# nixie_clock.net
KiCad netlist of a schematic drawn in EAGLE
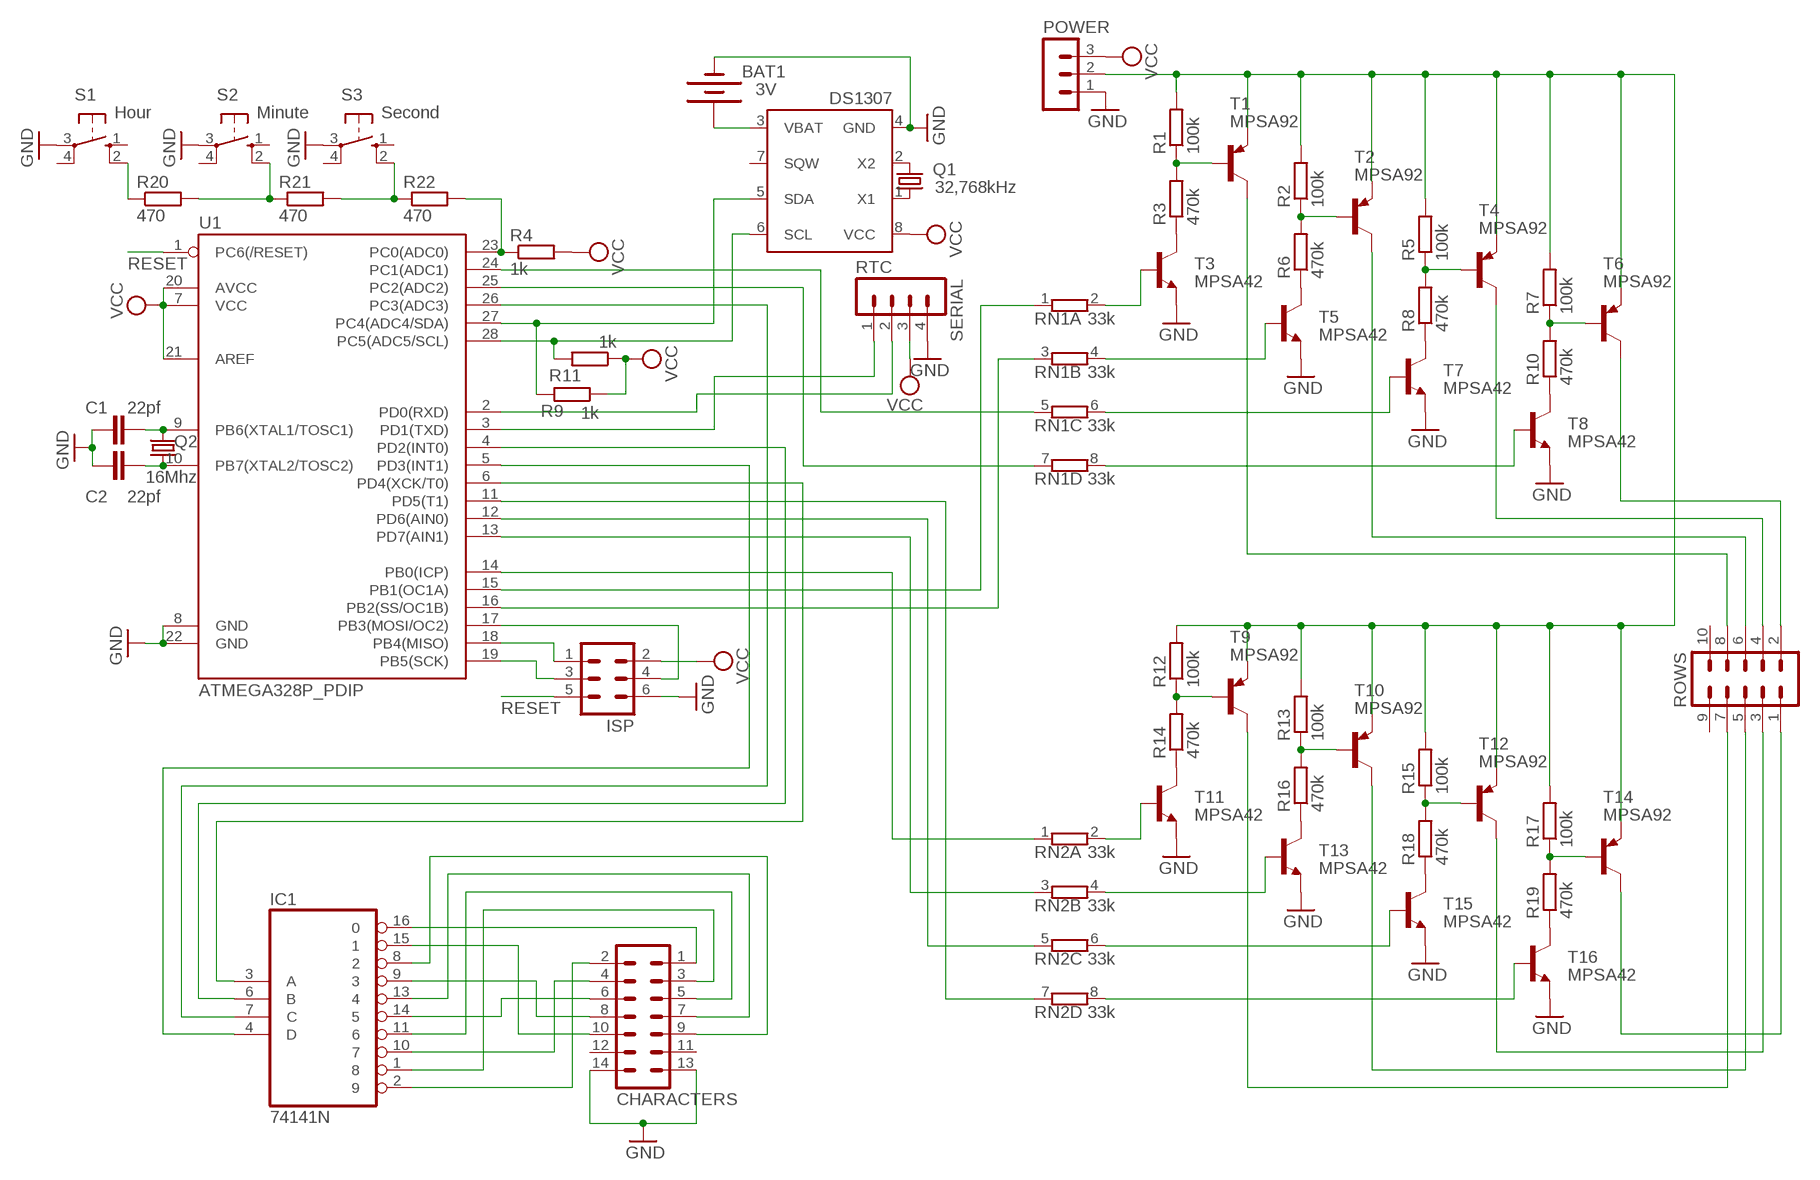
[diagram p0: schematic, sheet 1]

(export (version "E")
  (design (tool "Eeschema 10.0.6"))
  (components
    (comp (ref "BAT1")
      (value "3V")
      (footprint "eagle-import:BATTCOM_20MM_PTH")
      (libsource (lib "eagle-import") (part "BATTERY20PTH"))
    )
    (comp (ref "C1")
      (value "22pf")
      (footprint "eagle-import:CAP-PTH-SMALLEZ")
      (libsource (lib "eagle-import") (part "CAPEZ"))
    )
    (comp (ref "C2")
      (value "22pf")
      (footprint "eagle-import:CAP-PTH-SMALLEZ")
      (libsource (lib "eagle-import") (part "CAPEZ"))
    )
    (comp (ref "CHARACTERS")
      (value "MA07-2")
      (footprint "eagle-import:MA07-2")
      (libsource (lib "eagle-import") (part "MA07-2"))
    )
    (comp (ref "IC1")
      (value "74141N")
      (footprint "eagle-import:DIL16")
      (libsource (lib "eagle-import") (part "74141N"))
    )
    (comp (ref "ISP")
      (value "MA03-2")
      (footprint "eagle-import:MA03-2")
      (libsource (lib "eagle-import") (part "MA03-2"))
    )
    (comp (ref "POWER")
      (value "MA03-1")
      (footprint "eagle-import:MA03-1")
      (libsource (lib "eagle-import") (part "MA03-1"))
    )
    (comp (ref "Q1")
      (value "32,768kHz")
      (footprint "eagle-import:TC26V")
      (libsource (lib "eagle-import") (part "CRYSTALTC26V"))
    )
    (comp (ref "Q2")
      (value "16Mhz")
      (footprint "eagle-import:HC49_S")
      (libsource (lib "eagle-import") (part "CRYSTALHC49S"))
    )
    (comp (ref "R1")
      (value "100k")
      (footprint "eagle-import:0207_2V")
      (libsource (lib "eagle-import") (part "R-EU_0207/2V"))
    )
    (comp (ref "R2")
      (value "100k")
      (footprint "eagle-import:0207_2V")
      (libsource (lib "eagle-import") (part "R-EU_0207/2V"))
    )
    (comp (ref "R3")
      (value "470k")
      (footprint "eagle-import:0204_7")
      (libsource (lib "eagle-import") (part "R-EU_0204/7"))
    )
    (comp (ref "R4")
      (value "1k")
      (footprint "eagle-import:0204_7")
      (libsource (lib "eagle-import") (part "R-EU_0204/7"))
    )
    (comp (ref "R5")
      (value "100k")
      (footprint "eagle-import:0207_2V")
      (libsource (lib "eagle-import") (part "R-EU_0207/2V"))
    )
    (comp (ref "R6")
      (value "470k")
      (footprint "eagle-import:0204_7")
      (libsource (lib "eagle-import") (part "R-EU_0204/7"))
    )
    (comp (ref "R7")
      (value "100k")
      (footprint "eagle-import:0207_2V")
      (libsource (lib "eagle-import") (part "R-EU_0207/2V"))
    )
    (comp (ref "R8")
      (value "470k")
      (footprint "eagle-import:0204_7")
      (libsource (lib "eagle-import") (part "R-EU_0204/7"))
    )
    (comp (ref "R9")
      (value "1k")
      (footprint "eagle-import:0204_7")
      (libsource (lib "eagle-import") (part "R-EU_0204/7"))
    )
    (comp (ref "R10")
      (value "470k")
      (footprint "eagle-import:0204_7")
      (libsource (lib "eagle-import") (part "R-EU_0204/7"))
    )
    (comp (ref "R11")
      (value "1k")
      (footprint "eagle-import:0204_7")
      (libsource (lib "eagle-import") (part "R-EU_0204/7"))
    )
    (comp (ref "R12")
      (value "100k")
      (footprint "eagle-import:0207_2V")
      (libsource (lib "eagle-import") (part "R-EU_0207/2V"))
    )
    (comp (ref "R13")
      (value "100k")
      (footprint "eagle-import:0207_2V")
      (libsource (lib "eagle-import") (part "R-EU_0207/2V"))
    )
    (comp (ref "R14")
      (value "470k")
      (footprint "eagle-import:0204_7")
      (libsource (lib "eagle-import") (part "R-EU_0204/7"))
    )
    (comp (ref "R15")
      (value "100k")
      (footprint "eagle-import:0207_2V")
      (libsource (lib "eagle-import") (part "R-EU_0207/2V"))
    )
    (comp (ref "R16")
      (value "470k")
      (footprint "eagle-import:0204_7")
      (libsource (lib "eagle-import") (part "R-EU_0204/7"))
    )
    (comp (ref "R17")
      (value "100k")
      (footprint "eagle-import:0207_2V")
      (libsource (lib "eagle-import") (part "R-EU_0207/2V"))
    )
    (comp (ref "R18")
      (value "470k")
      (footprint "eagle-import:0204_7")
      (libsource (lib "eagle-import") (part "R-EU_0204/7"))
    )
    (comp (ref "R19")
      (value "470k")
      (footprint "eagle-import:0204_7")
      (libsource (lib "eagle-import") (part "R-EU_0204/7"))
    )
    (comp (ref "R20")
      (value "470")
      (footprint "eagle-import:0204_7")
      (libsource (lib "eagle-import") (part "R-EU_0204/7"))
    )
    (comp (ref "R21")
      (value "470")
      (footprint "eagle-import:0204_7")
      (libsource (lib "eagle-import") (part "R-EU_0204/7"))
    )
    (comp (ref "R22")
      (value "470")
      (footprint "eagle-import:0204_7")
      (libsource (lib "eagle-import") (part "R-EU_0204/7"))
    )
    (comp (ref "RN1")
      (value "33k")
      (footprint "eagle-import:SIL8")
      (libsource (lib "eagle-import") (part "E4R"))
    )
    (comp (ref "RN2")
      (value "33k")
      (footprint "eagle-import:SIL8")
      (libsource (lib "eagle-import") (part "E4R"))
    )
    (comp (ref "ROWS")
      (value "MA05-2")
      (footprint "eagle-import:MA05-2")
      (libsource (lib "eagle-import") (part "MA05-2"))
    )
    (comp (ref "RTC")
      (value "DS1307")
      (footprint "eagle-import:DIL08")
      (libsource (lib "eagle-import") (part "DS1307"))
    )
    (comp (ref "S1")
      (value "Hour")
      (footprint "eagle-import:B3F-10XX")
      (fields (field (name "MPN") "B3F-1000"))
      (libsource (lib "eagle-import") (part "10-XX"))
    )
    (comp (ref "S2")
      (value "Minute")
      (footprint "eagle-import:B3F-10XX")
      (fields (field (name "MPN") "B3F-1000"))
      (libsource (lib "eagle-import") (part "10-XX"))
    )
    (comp (ref "S3")
      (value "Second")
      (footprint "eagle-import:B3F-10XX")
      (fields (field (name "MPN") "B3F-1000"))
      (libsource (lib "eagle-import") (part "10-XX"))
    )
    (comp (ref "SERIAL")
      (value "MA04-1")
      (footprint "eagle-import:MA04-1")
      (libsource (lib "eagle-import") (part "MA04-1"))
    )
    (comp (ref "T1")
      (value "MPSA92")
      (footprint "eagle-import:TO92-EBC")
      (libsource (lib "eagle-import") (part "-PNP-TO92-EBCMPSA92"))
    )
    (comp (ref "T2")
      (value "MPSA92")
      (footprint "eagle-import:TO92-EBC")
      (libsource (lib "eagle-import") (part "-PNP-TO92-EBCMPSA92"))
    )
    (comp (ref "T3")
      (value "MPSA42")
      (footprint "eagle-import:TO92-EBC")
      (libsource (lib "eagle-import") (part "-NPN-TO92-EBCMPSA42"))
    )
    (comp (ref "T4")
      (value "MPSA92")
      (footprint "eagle-import:TO92-EBC")
      (libsource (lib "eagle-import") (part "-PNP-TO92-EBCMPSA92"))
    )
    (comp (ref "T5")
      (value "MPSA42")
      (footprint "eagle-import:TO92-EBC")
      (libsource (lib "eagle-import") (part "-NPN-TO92-EBCMPSA42"))
    )
    (comp (ref "T6")
      (value "MPSA92")
      (footprint "eagle-import:TO92-EBC")
      (libsource (lib "eagle-import") (part "-PNP-TO92-EBCMPSA92"))
    )
    (comp (ref "T7")
      (value "MPSA42")
      (footprint "eagle-import:TO92-EBC")
      (libsource (lib "eagle-import") (part "-NPN-TO92-EBCMPSA42"))
    )
    (comp (ref "T8")
      (value "MPSA42")
      (footprint "eagle-import:TO92-EBC")
      (libsource (lib "eagle-import") (part "-NPN-TO92-EBCMPSA42"))
    )
    (comp (ref "T9")
      (value "MPSA92")
      (footprint "eagle-import:TO92-EBC")
      (libsource (lib "eagle-import") (part "-PNP-TO92-EBCMPSA92"))
    )
    (comp (ref "T10")
      (value "MPSA92")
      (footprint "eagle-import:TO92-EBC")
      (libsource (lib "eagle-import") (part "-PNP-TO92-EBCMPSA92"))
    )
    (comp (ref "T11")
      (value "MPSA42")
      (footprint "eagle-import:TO92-EBC")
      (libsource (lib "eagle-import") (part "-NPN-TO92-EBCMPSA42"))
    )
    (comp (ref "T12")
      (value "MPSA92")
      (footprint "eagle-import:TO92-EBC")
      (libsource (lib "eagle-import") (part "-PNP-TO92-EBCMPSA92"))
    )
    (comp (ref "T13")
      (value "MPSA42")
      (footprint "eagle-import:TO92-EBC")
      (libsource (lib "eagle-import") (part "-NPN-TO92-EBCMPSA42"))
    )
    (comp (ref "T14")
      (value "MPSA92")
      (footprint "eagle-import:TO92-EBC")
      (libsource (lib "eagle-import") (part "-PNP-TO92-EBCMPSA92"))
    )
    (comp (ref "T15")
      (value "MPSA42")
      (footprint "eagle-import:TO92-EBC")
      (libsource (lib "eagle-import") (part "-NPN-TO92-EBCMPSA42"))
    )
    (comp (ref "T16")
      (value "MPSA42")
      (footprint "eagle-import:TO92-EBC")
      (libsource (lib "eagle-import") (part "-NPN-TO92-EBCMPSA42"))
    )
    (comp (ref "U1")
      (value "ATMEGA328P_PDIP")
      (footprint "eagle-import:DIL28-3")
      (libsource (lib "eagle-import") (part "ATMEGA328P_PDIP"))
    )
  )
  (nets
    (net (code "1") (name "/RESET") (class "Default")
      (node (ref "ISP") (pin "5") (pinfunction "5_5") (pintype "passive"))
      (node (ref "U1") (pin "1") (pinfunction "PC6(/RESET)_1") (pintype "bidirectional"))
    )
    (net (code "2") (name "GND") (class "Default")
      (node (ref "BAT1") (pin "2") (pinfunction "-_2") (pintype "power_in"))
      (node (ref "C1") (pin "1") (pinfunction "1_1") (pintype "passive"))
      (node (ref "C2") (pin "1") (pinfunction "1_1") (pintype "passive"))
      (node (ref "CHARACTERS") (pin "13") (pinfunction "13_13") (pintype "passive"))
      (node (ref "CHARACTERS") (pin "14") (pinfunction "14_14") (pintype "passive"))
      (node (ref "ISP") (pin "6") (pinfunction "6_6") (pintype "passive"))
      (node (ref "POWER") (pin "1") (pinfunction "1_1") (pintype "passive"))
      (node (ref "RTC") (pin "4") (pinfunction "GND_4") (pintype "power_in"))
      (node (ref "S1") (pin "3") (pinfunction "P_3") (pintype "passive"))
      (node (ref "S2") (pin "3") (pinfunction "P_3") (pintype "passive"))
      (node (ref "S3") (pin "3") (pinfunction "P_3") (pintype "passive"))
      (node (ref "SERIAL") (pin "4") (pinfunction "4_4") (pintype "passive"))
      (node (ref "T11") (pin "E") (pinfunction "E_E") (pintype "passive"))
      (node (ref "T13") (pin "E") (pinfunction "E_E") (pintype "passive"))
      (node (ref "T15") (pin "E") (pinfunction "E_E") (pintype "passive"))
      (node (ref "T16") (pin "E") (pinfunction "E_E") (pintype "passive"))
      (node (ref "T3") (pin "E") (pinfunction "E_E") (pintype "passive"))
      (node (ref "T5") (pin "E") (pinfunction "E_E") (pintype "passive"))
      (node (ref "T7") (pin "E") (pinfunction "E_E") (pintype "passive"))
      (node (ref "T8") (pin "E") (pinfunction "E_E") (pintype "passive"))
      (node (ref "U1") (pin "22") (pinfunction "GND_22") (pintype "bidirectional"))
      (node (ref "U1") (pin "8") (pinfunction "GND_8") (pintype "bidirectional"))
    )
    (net (code "3") (name "Net-(BAT1-+)") (class "Default")
      (node (ref "BAT1") (pin "1") (pinfunction "+_1") (pintype "power_in"))
      (node (ref "RTC") (pin "3") (pinfunction "VBAT_3") (pintype "passive"))
    )
    (net (code "4") (name "Net-(IC1A-0)") (class "Default")
      (node (ref "CHARACTERS") (pin "1") (pinfunction "1_1") (pintype "passive"))
      (node (ref "IC1") (pin "16") (pinfunction "0_16") (pintype "open_collector"))
    )
    (net (code "5") (name "Net-(IC1A-1)") (class "Default")
      (node (ref "CHARACTERS") (pin "10") (pinfunction "10_10") (pintype "passive"))
      (node (ref "IC1") (pin "15") (pinfunction "1_15") (pintype "open_collector"))
    )
    (net (code "6") (name "Net-(IC1A-2)") (class "Default")
      (node (ref "CHARACTERS") (pin "9") (pinfunction "9_9") (pintype "passive"))
      (node (ref "IC1") (pin "8") (pinfunction "2_8") (pintype "open_collector"))
    )
    (net (code "7") (name "Net-(IC1A-3)") (class "Default")
      (node (ref "CHARACTERS") (pin "8") (pinfunction "8_8") (pintype "passive"))
      (node (ref "IC1") (pin "9") (pinfunction "3_9") (pintype "open_collector"))
    )
    (net (code "8") (name "Net-(IC1A-4)") (class "Default")
      (node (ref "CHARACTERS") (pin "7") (pinfunction "7_7") (pintype "passive"))
      (node (ref "IC1") (pin "13") (pinfunction "4_13") (pintype "open_collector"))
    )
    (net (code "9") (name "Net-(IC1A-5)") (class "Default")
      (node (ref "CHARACTERS") (pin "6") (pinfunction "6_6") (pintype "passive"))
      (node (ref "IC1") (pin "14") (pinfunction "5_14") (pintype "open_collector"))
    )
    (net (code "10") (name "Net-(IC1A-6)") (class "Default")
      (node (ref "CHARACTERS") (pin "5") (pinfunction "5_5") (pintype "passive"))
      (node (ref "IC1") (pin "11") (pinfunction "6_11") (pintype "open_collector"))
    )
    (net (code "11") (name "Net-(IC1A-7)") (class "Default")
      (node (ref "CHARACTERS") (pin "4") (pinfunction "4_4") (pintype "passive"))
      (node (ref "IC1") (pin "10") (pinfunction "7_10") (pintype "open_collector"))
    )
    (net (code "12") (name "Net-(IC1A-8)") (class "Default")
      (node (ref "CHARACTERS") (pin "3") (pinfunction "3_3") (pintype "passive"))
      (node (ref "IC1") (pin "1") (pinfunction "8_1") (pintype "open_collector"))
    )
    (net (code "13") (name "Net-(IC1A-9)") (class "Default")
      (node (ref "CHARACTERS") (pin "2") (pinfunction "2_2") (pintype "passive"))
      (node (ref "IC1") (pin "2") (pinfunction "9_2") (pintype "open_collector"))
    )
    (net (code "14") (name "Net-(IC1A-A)") (class "Default")
      (node (ref "IC1") (pin "3") (pinfunction "A_3") (pintype "input"))
      (node (ref "U1") (pin "6") (pinfunction "PD4(XCK/T0)_6") (pintype "bidirectional"))
    )
    (net (code "15") (name "Net-(IC1A-B)") (class "Default")
      (node (ref "IC1") (pin "6") (pinfunction "B_6") (pintype "input"))
      (node (ref "U1") (pin "4") (pinfunction "PD2(INT0)_4") (pintype "bidirectional"))
    )
    (net (code "16") (name "Net-(IC1A-C)") (class "Default")
      (node (ref "IC1") (pin "7") (pinfunction "C_7") (pintype "input"))
      (node (ref "U1") (pin "26") (pinfunction "PC3(ADC3)_26") (pintype "bidirectional"))
    )
    (net (code "17") (name "Net-(IC1A-D)") (class "Default")
      (node (ref "IC1") (pin "4") (pinfunction "D_4") (pintype "input"))
      (node (ref "U1") (pin "5") (pinfunction "PD3(INT1)_5") (pintype "bidirectional"))
    )
    (net (code "18") (name "Net-(POWER-Pad2)") (class "Default")
      (node (ref "POWER") (pin "2") (pinfunction "2_2") (pintype "passive"))
      (node (ref "R1") (pin "2") (pinfunction "2_2") (pintype "passive"))
      (node (ref "R12") (pin "2") (pinfunction "2_2") (pintype "passive"))
      (node (ref "R13") (pin "2") (pinfunction "2_2") (pintype "passive"))
      (node (ref "R15") (pin "2") (pinfunction "2_2") (pintype "passive"))
      (node (ref "R17") (pin "2") (pinfunction "2_2") (pintype "passive"))
      (node (ref "R2") (pin "2") (pinfunction "2_2") (pintype "passive"))
      (node (ref "R5") (pin "2") (pinfunction "2_2") (pintype "passive"))
      (node (ref "R7") (pin "2") (pinfunction "2_2") (pintype "passive"))
      (node (ref "T1") (pin "E") (pinfunction "E_E") (pintype "passive"))
      (node (ref "T10") (pin "E") (pinfunction "E_E") (pintype "passive"))
      (node (ref "T12") (pin "E") (pinfunction "E_E") (pintype "passive"))
      (node (ref "T14") (pin "E") (pinfunction "E_E") (pintype "passive"))
      (node (ref "T2") (pin "E") (pinfunction "E_E") (pintype "passive"))
      (node (ref "T4") (pin "E") (pinfunction "E_E") (pintype "passive"))
      (node (ref "T6") (pin "E") (pinfunction "E_E") (pintype "passive"))
      (node (ref "T9") (pin "E") (pinfunction "E_E") (pintype "passive"))
    )
    (net (code "19") (name "Net-(R1-Pad1)") (class "Default")
      (node (ref "R1") (pin "1") (pinfunction "1_1") (pintype "passive"))
      (node (ref "R3") (pin "2") (pinfunction "2_2") (pintype "passive"))
      (node (ref "T1") (pin "B") (pinfunction "B_B") (pintype "passive"))
    )
    (net (code "20") (name "Net-(R2-Pad1)") (class "Default")
      (node (ref "R2") (pin "1") (pinfunction "1_1") (pintype "passive"))
      (node (ref "R6") (pin "2") (pinfunction "2_2") (pintype "passive"))
      (node (ref "T2") (pin "B") (pinfunction "B_B") (pintype "passive"))
    )
    (net (code "21") (name "Net-(R3-Pad1)") (class "Default")
      (node (ref "R3") (pin "1") (pinfunction "1_1") (pintype "passive"))
      (node (ref "T3") (pin "C") (pinfunction "C_C") (pintype "passive"))
    )
    (net (code "22") (name "Net-(R5-Pad1)") (class "Default")
      (node (ref "R5") (pin "1") (pinfunction "1_1") (pintype "passive"))
      (node (ref "R8") (pin "2") (pinfunction "2_2") (pintype "passive"))
      (node (ref "T4") (pin "B") (pinfunction "B_B") (pintype "passive"))
    )
    (net (code "23") (name "Net-(R6-Pad1)") (class "Default")
      (node (ref "R6") (pin "1") (pinfunction "1_1") (pintype "passive"))
      (node (ref "T5") (pin "C") (pinfunction "C_C") (pintype "passive"))
    )
    (net (code "24") (name "Net-(R8-Pad1)") (class "Default")
      (node (ref "R8") (pin "1") (pinfunction "1_1") (pintype "passive"))
      (node (ref "T7") (pin "C") (pinfunction "C_C") (pintype "passive"))
    )
    (net (code "25") (name "Net-(R10-Pad1)") (class "Default")
      (node (ref "R10") (pin "1") (pinfunction "1_1") (pintype "passive"))
      (node (ref "T8") (pin "C") (pinfunction "C_C") (pintype "passive"))
    )
    (net (code "26") (name "Net-(R10-Pad2)") (class "Default")
      (node (ref "R10") (pin "2") (pinfunction "2_2") (pintype "passive"))
      (node (ref "R7") (pin "1") (pinfunction "1_1") (pintype "passive"))
      (node (ref "T6") (pin "B") (pinfunction "B_B") (pintype "passive"))
    )
    (net (code "27") (name "Net-(R12-Pad1)") (class "Default")
      (node (ref "R12") (pin "1") (pinfunction "1_1") (pintype "passive"))
      (node (ref "R14") (pin "2") (pinfunction "2_2") (pintype "passive"))
      (node (ref "T9") (pin "B") (pinfunction "B_B") (pintype "passive"))
    )
    (net (code "28") (name "Net-(R13-Pad1)") (class "Default")
      (node (ref "R13") (pin "1") (pinfunction "1_1") (pintype "passive"))
      (node (ref "R16") (pin "2") (pinfunction "2_2") (pintype "passive"))
      (node (ref "T10") (pin "B") (pinfunction "B_B") (pintype "passive"))
    )
    (net (code "29") (name "Net-(R14-Pad1)") (class "Default")
      (node (ref "R14") (pin "1") (pinfunction "1_1") (pintype "passive"))
      (node (ref "T11") (pin "C") (pinfunction "C_C") (pintype "passive"))
    )
    (net (code "30") (name "Net-(R15-Pad1)") (class "Default")
      (node (ref "R15") (pin "1") (pinfunction "1_1") (pintype "passive"))
      (node (ref "R18") (pin "2") (pinfunction "2_2") (pintype "passive"))
      (node (ref "T12") (pin "B") (pinfunction "B_B") (pintype "passive"))
    )
    (net (code "31") (name "Net-(R16-Pad1)") (class "Default")
      (node (ref "R16") (pin "1") (pinfunction "1_1") (pintype "passive"))
      (node (ref "T13") (pin "C") (pinfunction "C_C") (pintype "passive"))
    )
    (net (code "32") (name "Net-(R17-Pad1)") (class "Default")
      (node (ref "R17") (pin "1") (pinfunction "1_1") (pintype "passive"))
      (node (ref "R19") (pin "2") (pinfunction "2_2") (pintype "passive"))
      (node (ref "T14") (pin "B") (pinfunction "B_B") (pintype "passive"))
    )
    (net (code "33") (name "Net-(R18-Pad1)") (class "Default")
      (node (ref "R18") (pin "1") (pinfunction "1_1") (pintype "passive"))
      (node (ref "T15") (pin "C") (pinfunction "C_C") (pintype "passive"))
    )
    (net (code "34") (name "Net-(R19-Pad1)") (class "Default")
      (node (ref "R19") (pin "1") (pinfunction "1_1") (pintype "passive"))
      (node (ref "T16") (pin "C") (pinfunction "C_C") (pintype "passive"))
    )
    (net (code "35") (name "Net-(RN1-Pad2)") (class "Default")
      (node (ref "RN1") (pin "2") (pinfunction "2_2") (pintype "passive"))
      (node (ref "T3") (pin "B") (pinfunction "B_B") (pintype "passive"))
    )
    (net (code "36") (name "Net-(RN1B-1)") (class "Default")
      (node (ref "RN1") (pin "3") (pinfunction "1_3") (pintype "passive"))
      (node (ref "U1") (pin "16") (pinfunction "PB2(SS/OC1B)_16") (pintype "bidirectional"))
    )
    (net (code "37") (name "Net-(RN1B-2)") (class "Default")
      (node (ref "RN1") (pin "4") (pinfunction "2_4") (pintype "passive"))
      (node (ref "T5") (pin "B") (pinfunction "B_B") (pintype "passive"))
    )
    (net (code "38") (name "Net-(RN1C-1)") (class "Default")
      (node (ref "RN1") (pin "5") (pinfunction "1_5") (pintype "passive"))
      (node (ref "U1") (pin "24") (pinfunction "PC1(ADC1)_24") (pintype "bidirectional"))
    )
    (net (code "39") (name "Net-(RN1C-2)") (class "Default")
      (node (ref "RN1") (pin "6") (pinfunction "2_6") (pintype "passive"))
      (node (ref "T7") (pin "B") (pinfunction "B_B") (pintype "passive"))
    )
    (net (code "40") (name "Net-(RN1D-1)") (class "Default")
      (node (ref "RN1") (pin "7") (pinfunction "1_7") (pintype "passive"))
      (node (ref "U1") (pin "25") (pinfunction "PC2(ADC2)_25") (pintype "bidirectional"))
    )
    (net (code "41") (name "Net-(RN1D-2)") (class "Default")
      (node (ref "RN1") (pin "8") (pinfunction "2_8") (pintype "passive"))
      (node (ref "T8") (pin "B") (pinfunction "B_B") (pintype "passive"))
    )
    (net (code "42") (name "Net-(RN2-Pad2)") (class "Default")
      (node (ref "RN2") (pin "2") (pinfunction "2_2") (pintype "passive"))
      (node (ref "T11") (pin "B") (pinfunction "B_B") (pintype "passive"))
    )
    (net (code "43") (name "Net-(RN2B-1)") (class "Default")
      (node (ref "RN2") (pin "3") (pinfunction "1_3") (pintype "passive"))
      (node (ref "U1") (pin "13") (pinfunction "PD7(AIN1)_13") (pintype "bidirectional"))
    )
    (net (code "44") (name "Net-(RN2B-2)") (class "Default")
      (node (ref "RN2") (pin "4") (pinfunction "2_4") (pintype "passive"))
      (node (ref "T13") (pin "B") (pinfunction "B_B") (pintype "passive"))
    )
    (net (code "45") (name "Net-(RN2C-1)") (class "Default")
      (node (ref "RN2") (pin "5") (pinfunction "1_5") (pintype "passive"))
      (node (ref "U1") (pin "12") (pinfunction "PD6(AIN0)_12") (pintype "bidirectional"))
    )
    (net (code "46") (name "Net-(RN2C-2)") (class "Default")
      (node (ref "RN2") (pin "6") (pinfunction "2_6") (pintype "passive"))
      (node (ref "T15") (pin "B") (pinfunction "B_B") (pintype "passive"))
    )
    (net (code "47") (name "Net-(RN2D-1)") (class "Default")
      (node (ref "RN2") (pin "7") (pinfunction "1_7") (pintype "passive"))
      (node (ref "U1") (pin "11") (pinfunction "PD5(T1)_11") (pintype "bidirectional"))
    )
    (net (code "48") (name "Net-(RN2D-2)") (class "Default")
      (node (ref "RN2") (pin "8") (pinfunction "2_8") (pintype "passive"))
      (node (ref "T16") (pin "B") (pinfunction "B_B") (pintype "passive"))
    )
    (net (code "49") (name "Net-(ROWS-Pad1)") (class "Default")
      (node (ref "ROWS") (pin "1") (pinfunction "1_1") (pintype "passive"))
      (node (ref "T14") (pin "C") (pinfunction "C_C") (pintype "passive"))
    )
    (net (code "50") (name "Net-(ROWS-Pad2)") (class "Default")
      (node (ref "ROWS") (pin "2") (pinfunction "2_2") (pintype "passive"))
      (node (ref "T6") (pin "C") (pinfunction "C_C") (pintype "passive"))
    )
    (net (code "51") (name "Net-(ROWS-Pad3)") (class "Default")
      (node (ref "ROWS") (pin "3") (pinfunction "3_3") (pintype "passive"))
      (node (ref "T12") (pin "C") (pinfunction "C_C") (pintype "passive"))
    )
    (net (code "52") (name "Net-(ROWS-Pad4)") (class "Default")
      (node (ref "ROWS") (pin "4") (pinfunction "4_4") (pintype "passive"))
      (node (ref "T4") (pin "C") (pinfunction "C_C") (pintype "passive"))
    )
    (net (code "53") (name "Net-(ROWS-Pad5)") (class "Default")
      (node (ref "ROWS") (pin "5") (pinfunction "5_5") (pintype "passive"))
      (node (ref "T10") (pin "C") (pinfunction "C_C") (pintype "passive"))
    )
    (net (code "54") (name "Net-(ROWS-Pad6)") (class "Default")
      (node (ref "ROWS") (pin "6") (pinfunction "6_6") (pintype "passive"))
      (node (ref "T2") (pin "C") (pinfunction "C_C") (pintype "passive"))
    )
    (net (code "55") (name "Net-(ROWS-Pad7)") (class "Default")
      (node (ref "ROWS") (pin "7") (pinfunction "7_7") (pintype "passive"))
      (node (ref "T9") (pin "C") (pinfunction "C_C") (pintype "passive"))
    )
    (net (code "56") (name "Net-(ROWS-Pad8)") (class "Default")
      (node (ref "ROWS") (pin "8") (pinfunction "8_8") (pintype "passive"))
      (node (ref "T1") (pin "C") (pinfunction "C_C") (pintype "passive"))
    )
    (net (code "57") (name "Net-(RTC-SCL)") (class "Default")
      (node (ref "R11") (pin "2") (pinfunction "2_2") (pintype "passive"))
      (node (ref "RTC") (pin "6") (pinfunction "SCL_6") (pintype "input"))
      (node (ref "U1") (pin "28") (pinfunction "PC5(ADC5/SCL)_28") (pintype "bidirectional"))
    )
    (net (code "58") (name "Net-(RTC-SDA)") (class "Default")
      (node (ref "R9") (pin "2") (pinfunction "2_2") (pintype "passive"))
      (node (ref "RTC") (pin "5") (pinfunction "SDA_5") (pintype "bidirectional"))
      (node (ref "U1") (pin "27") (pinfunction "PC4(ADC4/SDA)_27") (pintype "bidirectional"))
    )
    (net (code "59") (name "Net-(RTC-X1)") (class "Default")
      (node (ref "Q1") (pin "1") (pinfunction "1_1") (pintype "passive"))
      (node (ref "RTC") (pin "1") (pinfunction "X1_1") (pintype "input"))
    )
    (net (code "60") (name "Net-(RTC-X2)") (class "Default")
      (node (ref "Q1") (pin "2") (pinfunction "2_2") (pintype "passive"))
      (node (ref "RTC") (pin "2") (pinfunction "X2_2") (pintype "output"))
    )
    (net (code "61") (name "Net-(S1-S1)") (class "Default")
      (node (ref "R20") (pin "1") (pinfunction "1_1") (pintype "passive"))
      (node (ref "S1") (pin "2") (pinfunction "S1_2") (pintype "passive"))
    )
    (net (code "62") (name "Net-(S2-S1)") (class "Default")
      (node (ref "R20") (pin "2") (pinfunction "2_2") (pintype "passive"))
      (node (ref "R21") (pin "1") (pinfunction "1_1") (pintype "passive"))
      (node (ref "S2") (pin "2") (pinfunction "S1_2") (pintype "passive"))
    )
    (net (code "63") (name "Net-(S3-S1)") (class "Default")
      (node (ref "R21") (pin "2") (pinfunction "2_2") (pintype "passive"))
      (node (ref "R22") (pin "1") (pinfunction "1_1") (pintype "passive"))
      (node (ref "S3") (pin "2") (pinfunction "S1_2") (pintype "passive"))
    )
    (net (code "64") (name "Net-(U1-PB0(ICP))") (class "Default")
      (node (ref "RN2") (pin "1") (pinfunction "1_1") (pintype "passive"))
      (node (ref "U1") (pin "14") (pinfunction "PB0(ICP)_14") (pintype "bidirectional"))
    )
    (net (code "65") (name "Net-(U1-PB1(OC1A))") (class "Default")
      (node (ref "RN1") (pin "1") (pinfunction "1_1") (pintype "passive"))
      (node (ref "U1") (pin "15") (pinfunction "PB1(OC1A)_15") (pintype "bidirectional"))
    )
    (net (code "66") (name "Net-(U1-PB3(MOSI{slash}OC2))") (class "Default")
      (node (ref "ISP") (pin "4") (pinfunction "4_4") (pintype "passive"))
      (node (ref "U1") (pin "17") (pinfunction "PB3(MOSI/OC2)_17") (pintype "bidirectional"))
    )
    (net (code "67") (name "Net-(U1-PB4(MISO))") (class "Default")
      (node (ref "ISP") (pin "1") (pinfunction "1_1") (pintype "passive"))
      (node (ref "U1") (pin "18") (pinfunction "PB4(MISO)_18") (pintype "bidirectional"))
    )
    (net (code "68") (name "Net-(U1-PB5(SCK))") (class "Default")
      (node (ref "ISP") (pin "3") (pinfunction "3_3") (pintype "passive"))
      (node (ref "U1") (pin "19") (pinfunction "PB5(SCK)_19") (pintype "bidirectional"))
    )
    (net (code "69") (name "Net-(U1-PB6(XTAL1{slash}TOSC1))") (class "Default")
      (node (ref "C1") (pin "2") (pinfunction "2_2") (pintype "passive"))
      (node (ref "Q2") (pin "2") (pinfunction "2_2") (pintype "passive"))
      (node (ref "U1") (pin "9") (pinfunction "PB6(XTAL1/TOSC1)_9") (pintype "bidirectional"))
    )
    (net (code "70") (name "Net-(U1-PB7(XTAL2{slash}TOSC2))") (class "Default")
      (node (ref "C2") (pin "2") (pinfunction "2_2") (pintype "passive"))
      (node (ref "Q2") (pin "1") (pinfunction "1_1") (pintype "passive"))
      (node (ref "U1") (pin "10") (pinfunction "PB7(XTAL2/TOSC2)_10") (pintype "bidirectional"))
    )
    (net (code "71") (name "Net-(U1-PC0(ADC0))") (class "Default")
      (node (ref "R22") (pin "2") (pinfunction "2_2") (pintype "passive"))
      (node (ref "R4") (pin "1") (pinfunction "1_1") (pintype "passive"))
      (node (ref "U1") (pin "23") (pinfunction "PC0(ADC0)_23") (pintype "bidirectional"))
    )
    (net (code "72") (name "Net-(U1-PD0(RXD))") (class "Default")
      (node (ref "SERIAL") (pin "2") (pinfunction "2_2") (pintype "passive"))
      (node (ref "U1") (pin "2") (pinfunction "PD0(RXD)_2") (pintype "bidirectional"))
    )
    (net (code "73") (name "Net-(U1-PD1(TXD))") (class "Default")
      (node (ref "SERIAL") (pin "1") (pinfunction "1_1") (pintype "passive"))
      (node (ref "U1") (pin "3") (pinfunction "PD1(TXD)_3") (pintype "bidirectional"))
    )
    (net (code "74") (name "VCC") (class "Default")
      (node (ref "ISP") (pin "2") (pinfunction "2_2") (pintype "passive"))
      (node (ref "POWER") (pin "3") (pinfunction "3_3") (pintype "passive"))
      (node (ref "R11") (pin "1") (pinfunction "1_1") (pintype "passive"))
      (node (ref "R4") (pin "2") (pinfunction "2_2") (pintype "passive"))
      (node (ref "R9") (pin "1") (pinfunction "1_1") (pintype "passive"))
      (node (ref "RTC") (pin "8") (pinfunction "VCC_8") (pintype "power_in"))
      (node (ref "SERIAL") (pin "3") (pinfunction "3_3") (pintype "passive"))
      (node (ref "U1") (pin "20") (pinfunction "AVCC_20") (pintype "bidirectional"))
      (node (ref "U1") (pin "21") (pinfunction "AREF_21") (pintype "bidirectional"))
      (node (ref "U1") (pin "7") (pinfunction "VCC_7") (pintype "bidirectional"))
    )
    (net (code "75") (name "unconnected-(CHARACTERS-Pad11)") (class "Default")
      (node (ref "CHARACTERS") (pin "11") (pinfunction "11_11") (pintype "passive"))
    )
    (net (code "76") (name "unconnected-(CHARACTERS-Pad12)") (class "Default")
      (node (ref "CHARACTERS") (pin "12") (pinfunction "12_12") (pintype "passive"))
    )
    (net (code "77") (name "unconnected-(ROWS-Pad9)") (class "Default")
      (node (ref "ROWS") (pin "9") (pinfunction "9_9") (pintype "passive"))
    )
    (net (code "78") (name "unconnected-(ROWS-Pad10)") (class "Default")
      (node (ref "ROWS") (pin "10") (pinfunction "10_10") (pintype "passive"))
    )
    (net (code "79") (name "unconnected-(RTC-SQW-Pad7)") (class "Default")
      (node (ref "RTC") (pin "7") (pinfunction "SQW_7") (pintype "open_collector"))
    )
    (net (code "80") (name "unconnected-(S1-P1-Pad4)") (class "Default")
      (node (ref "S1") (pin "4") (pinfunction "P1_4") (pintype "passive"))
    )
    (net (code "81") (name "unconnected-(S1-S-Pad1)") (class "Default")
      (node (ref "S1") (pin "1") (pinfunction "S_1") (pintype "passive"))
    )
    (net (code "82") (name "unconnected-(S2-P1-Pad4)") (class "Default")
      (node (ref "S2") (pin "4") (pinfunction "P1_4") (pintype "passive"))
    )
    (net (code "83") (name "unconnected-(S2-S-Pad1)") (class "Default")
      (node (ref "S2") (pin "1") (pinfunction "S_1") (pintype "passive"))
    )
    (net (code "84") (name "unconnected-(S3-P1-Pad4)") (class "Default")
      (node (ref "S3") (pin "4") (pinfunction "P1_4") (pintype "passive"))
    )
    (net (code "85") (name "unconnected-(S3-S-Pad1)") (class "Default")
      (node (ref "S3") (pin "1") (pinfunction "S_1") (pintype "passive"))
    )
  )
)
